# md_ver10_1.net
KiCad netlist of a schematic drawn in EAGLE
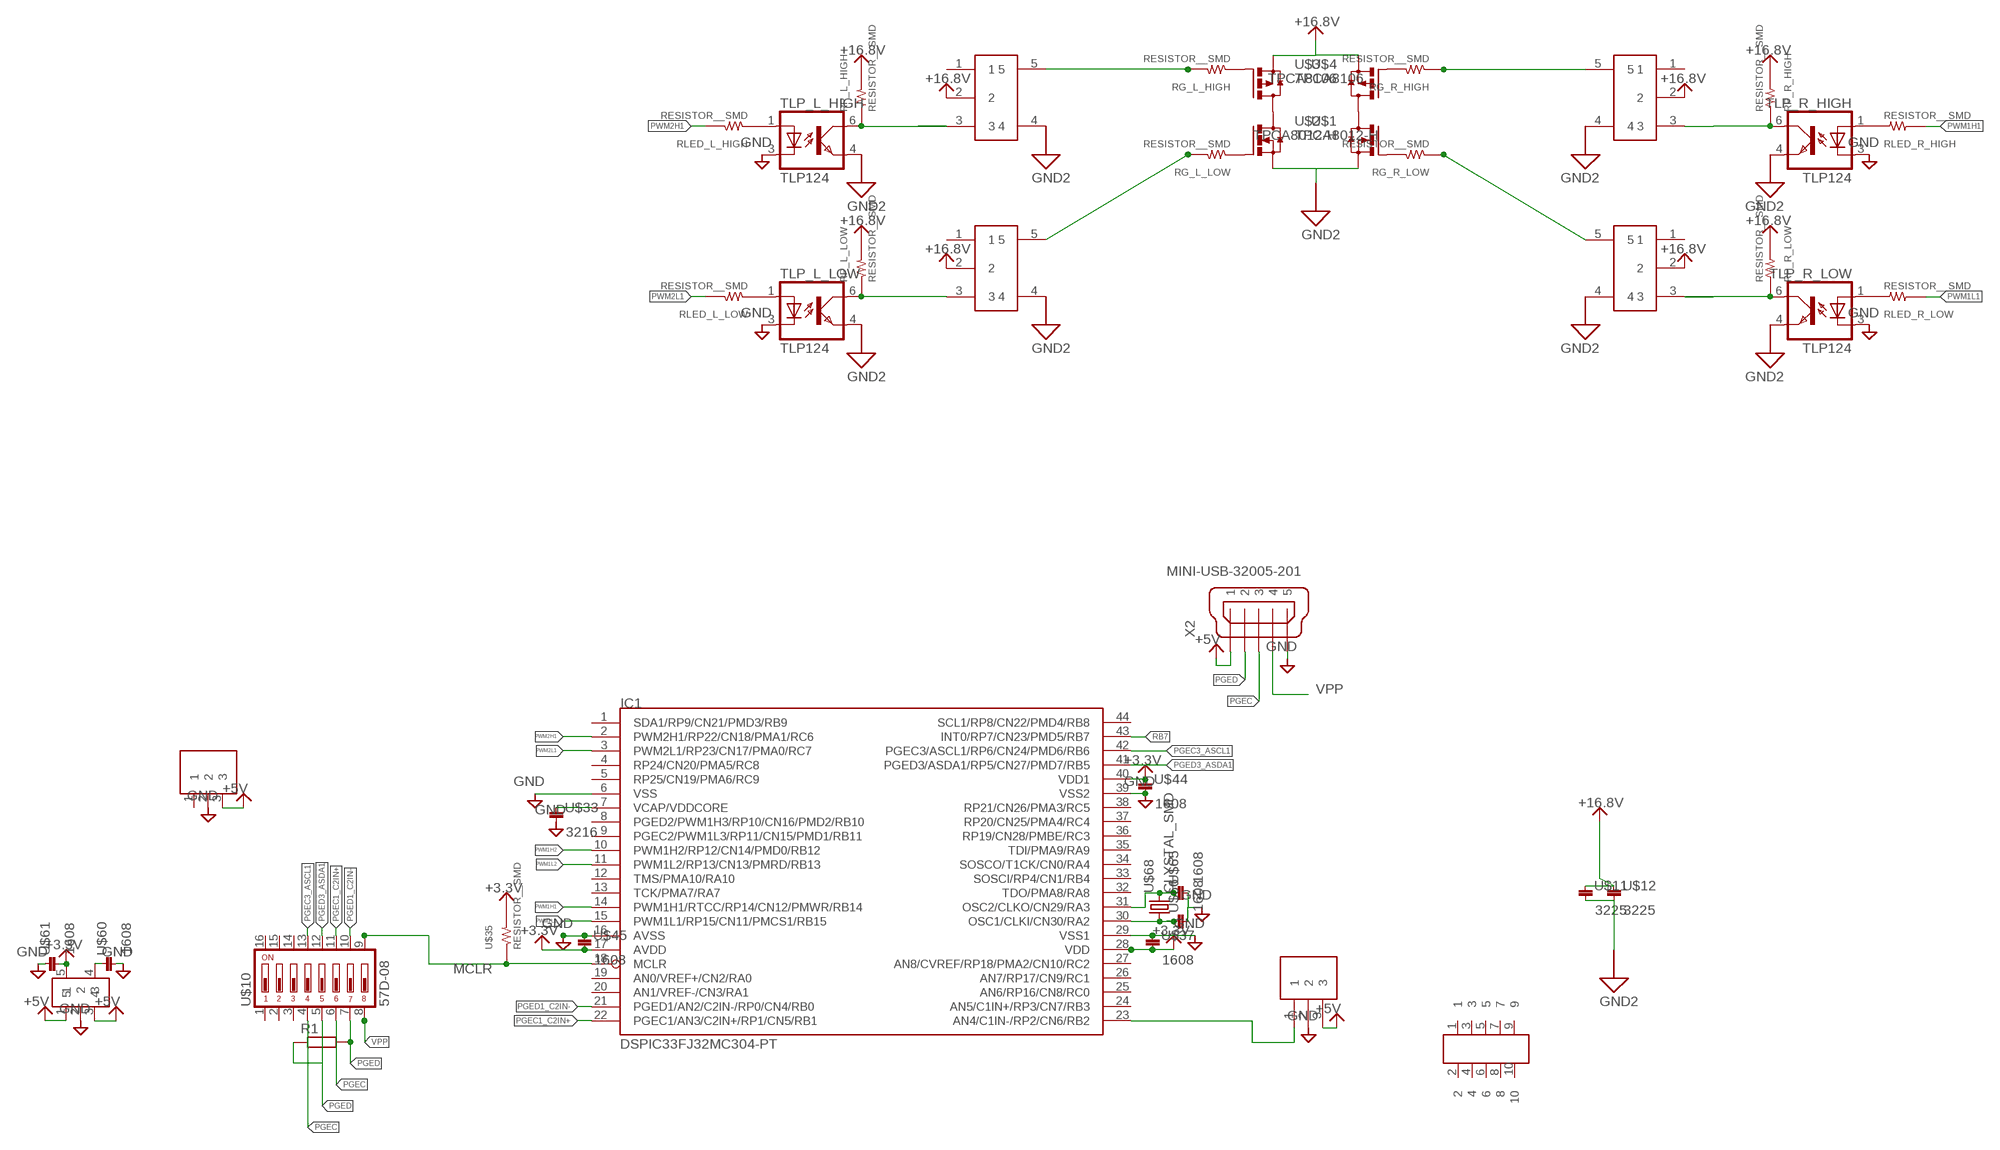
[diagram p0: schematic, sheet 1]

(export (version "E")
  (design (tool "Eeschema 10.0.6"))
  (components
    (comp (ref "IC1")
      (value "DSPIC33FJ32MC304-PT")
      (footprint "eagle-import:TQFP44")
      (libsource (lib "eagle-import") (part "DSPIC33FJ32MC304-PT"))
    )
    (comp (ref "IC_L_HIGH")
      (value "MCP1415")
      (footprint "eagle-import:SOT23-5L")
      (libsource (lib "eagle-import") (part "MCP1415"))
    )
    (comp (ref "IC_L_LOW")
      (value "MCP1415")
      (footprint "eagle-import:SOT23-5L")
      (libsource (lib "eagle-import") (part "MCP1415"))
    )
    (comp (ref "IC_R_HIGH")
      (value "MCP1415")
      (footprint "eagle-import:SOT23-5L")
      (libsource (lib "eagle-import") (part "MCP1415"))
    )
    (comp (ref "IC_R_LOW")
      (value "MCP1415")
      (footprint "eagle-import:SOT23-5L")
      (libsource (lib "eagle-import") (part "MCP1415"))
    )
    (comp (ref "R1")
      (value "R-EU_R3216")
      (footprint "eagle-import:R3216")
      (libsource (lib "eagle-import") (part "R-EU_R3216"))
    )
    (comp (ref "RG_L_HIGH")
      (value "RESISTOR__SMD")
      (footprint "eagle-import:1608")
      (libsource (lib "eagle-import") (part "RESISTOR__SMD"))
    )
    (comp (ref "RG_L_LOW")
      (value "RESISTOR__SMD")
      (footprint "eagle-import:1608")
      (libsource (lib "eagle-import") (part "RESISTOR__SMD"))
    )
    (comp (ref "RG_R_HIGH")
      (value "RESISTOR__SMD")
      (footprint "eagle-import:1608")
      (libsource (lib "eagle-import") (part "RESISTOR__SMD"))
    )
    (comp (ref "RG_R_LOW")
      (value "RESISTOR__SMD")
      (footprint "eagle-import:1608")
      (libsource (lib "eagle-import") (part "RESISTOR__SMD"))
    )
    (comp (ref "RLED_L_HIGH")
      (value "RESISTOR__SMD")
      (footprint "eagle-import:1608")
      (libsource (lib "eagle-import") (part "RESISTOR__SMD"))
    )
    (comp (ref "RLED_L_LOW")
      (value "RESISTOR__SMD")
      (footprint "eagle-import:1608")
      (libsource (lib "eagle-import") (part "RESISTOR__SMD"))
    )
    (comp (ref "RLED_R_HIGH")
      (value "RESISTOR__SMD")
      (footprint "eagle-import:1608")
      (libsource (lib "eagle-import") (part "RESISTOR__SMD"))
    )
    (comp (ref "RLED_R_LOW")
      (value "RESISTOR__SMD")
      (footprint "eagle-import:1608")
      (libsource (lib "eagle-import") (part "RESISTOR__SMD"))
    )
    (comp (ref "RP_L_HIGH")
      (value "RESISTOR__SMD")
      (footprint "eagle-import:1608")
      (libsource (lib "eagle-import") (part "RESISTOR__SMD"))
    )
    (comp (ref "RP_L_LOW")
      (value "RESISTOR__SMD")
      (footprint "eagle-import:1608")
      (libsource (lib "eagle-import") (part "RESISTOR__SMD"))
    )
    (comp (ref "RP_R_HIGH")
      (value "RESISTOR__SMD")
      (footprint "eagle-import:1608")
      (libsource (lib "eagle-import") (part "RESISTOR__SMD"))
    )
    (comp (ref "RP_R_LOW")
      (value "RESISTOR__SMD")
      (footprint "eagle-import:1608")
      (libsource (lib "eagle-import") (part "RESISTOR__SMD"))
    )
    (comp (ref "TLP_L_HIGH")
      (value "TLP124")
      (footprint "eagle-import:11−4C1")
      (libsource (lib "eagle-import") (part "TLP124"))
    )
    (comp (ref "TLP_L_LOW")
      (value "TLP124")
      (footprint "eagle-import:11−4C1")
      (libsource (lib "eagle-import") (part "TLP124"))
    )
    (comp (ref "TLP_R_HIGH")
      (value "TLP124")
      (footprint "eagle-import:11−4C1")
      (libsource (lib "eagle-import") (part "TLP124"))
    )
    (comp (ref "TLP_R_LOW")
      (value "TLP124")
      (footprint "eagle-import:11−4C1")
      (libsource (lib "eagle-import") (part "TLP124"))
    )
    (comp (ref "U$1")
      (value "TPCA8012-H")
      (footprint "eagle-import:2-5Q1A")
      (libsource (lib "eagle-import") (part "TPCA8012-H"))
    )
    (comp (ref "U$2")
      (value "TPCA8012-H")
      (footprint "eagle-import:2-5Q1A")
      (libsource (lib "eagle-import") (part "TPCA8012-H"))
    )
    (comp (ref "U$3")
      (value "TPCA8106")
      (footprint "eagle-import:2-5Q1A")
      (libsource (lib "eagle-import") (part "TPCA8106"))
    )
    (comp (ref "U$4")
      (value "TPCA8106")
      (footprint "eagle-import:2-5Q1A")
      (libsource (lib "eagle-import") (part "TPCA8106"))
    )
    (comp (ref "U$7")
      (value "ＰＬ－ＩＲＭ")
      (footprint "eagle-import:ＰＬ－ＩＲＭ")
      (libsource (lib "eagle-import") (part "ＰＬ－ＩＲＭ"))
    )
    (comp (ref "U$8")
      (value "Ｒ－７８Ｅ５．０")
      (footprint "eagle-import:Ｒ－７８Ｅ５．０")
      (libsource (lib "eagle-import") (part "Ｒ－７８Ｅ５．０"))
    )
    (comp (ref "U$9")
      (value "TAR5SB")
      (footprint "eagle-import:SSOP5-P-0.95")
      (libsource (lib "eagle-import") (part "TAR5SB"))
    )
    (comp (ref "U$10")
      (value "57D-08")
      (footprint "eagle-import:57D")
      (libsource (lib "eagle-import") (part "57D-08"))
    )
    (comp (ref "U$11")
      (value "3225")
      (footprint "eagle-import:3225")
      (libsource (lib "eagle-import") (part "3225"))
    )
    (comp (ref "U$12")
      (value "3225")
      (footprint "eagle-import:3225")
      (libsource (lib "eagle-import") (part "3225"))
    )
    (comp (ref "U$15")
      (value "PIN_HEADER_52")
      (footprint "eagle-import:PIN_HEADER_5_2")
      (libsource (lib "eagle-import") (part "PIN_HEADER_52"))
    )
    (comp (ref "U$33")
      (value "3216")
      (footprint "eagle-import:3216")
      (libsource (lib "eagle-import") (part "3216"))
    )
    (comp (ref "U$35")
      (value "RESISTOR__SMD")
      (footprint "eagle-import:1608")
      (libsource (lib "eagle-import") (part "RESISTOR__SMD"))
    )
    (comp (ref "U$37")
      (value "1608")
      (footprint "eagle-import:1608")
      (libsource (lib "eagle-import") (part "1608"))
    )
    (comp (ref "U$44")
      (value "1608")
      (footprint "eagle-import:1608")
      (libsource (lib "eagle-import") (part "1608"))
    )
    (comp (ref "U$45")
      (value "1608")
      (footprint "eagle-import:1608")
      (libsource (lib "eagle-import") (part "1608"))
    )
    (comp (ref "U$60")
      (value "1608")
      (footprint "eagle-import:1608")
      (libsource (lib "eagle-import") (part "1608"))
    )
    (comp (ref "U$61")
      (value "1608")
      (footprint "eagle-import:1608")
      (libsource (lib "eagle-import") (part "1608"))
    )
    (comp (ref "U$65")
      (value "1608")
      (footprint "eagle-import:1608")
      (libsource (lib "eagle-import") (part "1608"))
    )
    (comp (ref "U$66")
      (value "1608")
      (footprint "eagle-import:1608")
      (libsource (lib "eagle-import") (part "1608"))
    )
    (comp (ref "U$68")
      (value "CLYSTAL_SMD")
      (footprint "eagle-import:CRYSTAL_SMD")
      (libsource (lib "eagle-import") (part "CLYSTAL_SMD"))
    )
    (comp (ref "X2")
      (value "MINI-USB-32005-201")
      (footprint "eagle-import:32005-201")
      (libsource (lib "eagle-import") (part "MINI-USB-32005-201"))
    )
  )
  (nets
    (net (code "1") (name "+3.3V") (class "Default")
      (node (ref "IC1") (pin "17") (pinfunction "AVDD_17") (pintype "power_in"))
      (node (ref "IC1") (pin "28") (pinfunction "VDD_28") (pintype "power_in"))
      (node (ref "IC1") (pin "40") (pinfunction "VDD1_40") (pintype "power_in"))
      (node (ref "U$35") (pin "2") (pinfunction "P$2_2") (pintype "passive"))
      (node (ref "U$37") (pin "P$2") (pinfunction "2_P$2") (pintype "passive"))
      (node (ref "U$44") (pin "P$1") (pinfunction "1_P$1") (pintype "passive"))
      (node (ref "U$45") (pin "P$2") (pinfunction "2_P$2") (pintype "passive"))
      (node (ref "U$61") (pin "P$2") (pinfunction "2_P$2") (pintype "passive"))
      (node (ref "U$9") (pin "5") (pinfunction "5_5") (pintype "bidirectional"))
    )
    (net (code "2") (name "+5V") (class "Default")
      (node (ref "U$7") (pin "3") (pinfunction "3_3") (pintype "bidirectional"))
      (node (ref "U$8") (pin "3") (pinfunction "3_3") (pintype "bidirectional"))
      (node (ref "U$9") (pin "1") (pinfunction "1_1") (pintype "bidirectional"))
      (node (ref "U$9") (pin "3") (pinfunction "3_3") (pintype "bidirectional"))
      (node (ref "X2") (pin "1") (pinfunction "1_1") (pintype "passive"))
    )
    (net (code "3") (name "+16.8V") (class "Default")
      (node (ref "IC_L_HIGH") (pin "2") (pinfunction "2_2") (pintype "bidirectional"))
      (node (ref "IC_L_LOW") (pin "2") (pinfunction "2_2") (pintype "bidirectional"))
      (node (ref "IC_R_HIGH") (pin "2") (pinfunction "2_2") (pintype "bidirectional"))
      (node (ref "IC_R_LOW") (pin "2") (pinfunction "2_2") (pintype "bidirectional"))
      (node (ref "RP_L_HIGH") (pin "2") (pinfunction "P$2_2") (pintype "passive"))
      (node (ref "RP_L_LOW") (pin "2") (pinfunction "P$2_2") (pintype "passive"))
      (node (ref "RP_R_HIGH") (pin "2") (pinfunction "P$2_2") (pintype "passive"))
      (node (ref "RP_R_LOW") (pin "2") (pinfunction "P$2_2") (pintype "passive"))
      (node (ref "U$11") (pin "P$1") (pinfunction "1_P$1") (pintype "passive"))
      (node (ref "U$12") (pin "P$1") (pinfunction "1_P$1") (pintype "passive"))
      (node (ref "U$3") (pin "1") (pinfunction "S_1") (pintype "passive"))
      (node (ref "U$3") (pin "2") (pinfunction "S_2") (pintype "passive"))
      (node (ref "U$3") (pin "3") (pinfunction "S_3") (pintype "passive"))
      (node (ref "U$4") (pin "1") (pinfunction "S_1") (pintype "passive"))
      (node (ref "U$4") (pin "2") (pinfunction "S_2") (pintype "passive"))
      (node (ref "U$4") (pin "3") (pinfunction "S_3") (pintype "passive"))
    )
    (net (code "4") (name "/MCLR") (class "Default")
      (node (ref "IC1") (pin "18") (pinfunction "MCLR_18") (pintype "input"))
      (node (ref "U$10") (pin "9") (pinfunction "9_9") (pintype "passive"))
      (node (ref "U$35") (pin "1") (pinfunction "P$1_1") (pintype "passive"))
    )
    (net (code "5") (name "GND") (class "Default")
      (node (ref "IC1") (pin "16") (pinfunction "AVSS_16") (pintype "power_in"))
      (node (ref "IC1") (pin "29") (pinfunction "VSS1_29") (pintype "power_in"))
      (node (ref "IC1") (pin "39") (pinfunction "VSS2_39") (pintype "power_in"))
      (node (ref "IC1") (pin "6") (pinfunction "VSS_6") (pintype "power_in"))
      (node (ref "TLP_L_HIGH") (pin "3") (pinfunction "C_3") (pintype "passive"))
      (node (ref "TLP_L_LOW") (pin "3") (pinfunction "C_3") (pintype "passive"))
      (node (ref "TLP_R_HIGH") (pin "3") (pinfunction "C_3") (pintype "passive"))
      (node (ref "TLP_R_LOW") (pin "3") (pinfunction "C_3") (pintype "passive"))
      (node (ref "U$33") (pin "P$2") (pinfunction "2_P$2") (pintype "passive"))
      (node (ref "U$37") (pin "P$1") (pinfunction "1_P$1") (pintype "passive"))
      (node (ref "U$44") (pin "P$2") (pinfunction "2_P$2") (pintype "passive"))
      (node (ref "U$45") (pin "P$1") (pinfunction "1_P$1") (pintype "passive"))
      (node (ref "U$60") (pin "P$2") (pinfunction "2_P$2") (pintype "passive"))
      (node (ref "U$61") (pin "P$1") (pinfunction "1_P$1") (pintype "passive"))
      (node (ref "U$65") (pin "P$2") (pinfunction "2_P$2") (pintype "passive"))
      (node (ref "U$66") (pin "P$2") (pinfunction "2_P$2") (pintype "passive"))
      (node (ref "U$7") (pin "2") (pinfunction "2_2") (pintype "bidirectional"))
      (node (ref "U$8") (pin "2") (pinfunction "2_2") (pintype "bidirectional"))
      (node (ref "U$9") (pin "2") (pinfunction "2_2") (pintype "bidirectional"))
      (node (ref "X2") (pin "5") (pinfunction "5_5") (pintype "passive"))
    )
    (net (code "6") (name "GND2") (class "Default")
      (node (ref "IC_L_HIGH") (pin "4") (pinfunction "4_4") (pintype "bidirectional"))
      (node (ref "IC_L_LOW") (pin "4") (pinfunction "4_4") (pintype "bidirectional"))
      (node (ref "IC_R_HIGH") (pin "4") (pinfunction "4_4") (pintype "bidirectional"))
      (node (ref "IC_R_LOW") (pin "4") (pinfunction "4_4") (pintype "bidirectional"))
      (node (ref "TLP_L_HIGH") (pin "4") (pinfunction "EMIT_4") (pintype "passive"))
      (node (ref "TLP_L_LOW") (pin "4") (pinfunction "EMIT_4") (pintype "passive"))
      (node (ref "TLP_R_HIGH") (pin "4") (pinfunction "EMIT_4") (pintype "passive"))
      (node (ref "TLP_R_LOW") (pin "4") (pinfunction "EMIT_4") (pintype "passive"))
      (node (ref "U$1") (pin "1") (pinfunction "S_1") (pintype "passive"))
      (node (ref "U$1") (pin "2") (pinfunction "S_2") (pintype "passive"))
      (node (ref "U$1") (pin "3") (pinfunction "S_3") (pintype "passive"))
      (node (ref "U$11") (pin "P$2") (pinfunction "2_P$2") (pintype "passive"))
      (node (ref "U$12") (pin "P$2") (pinfunction "2_P$2") (pintype "passive"))
      (node (ref "U$2") (pin "1") (pinfunction "S_1") (pintype "passive"))
      (node (ref "U$2") (pin "2") (pinfunction "S_2") (pintype "passive"))
      (node (ref "U$2") (pin "3") (pinfunction "S_3") (pintype "passive"))
    )
    (net (code "7") (name "Net-(IC1-AN4{slash}C1IN-{slash}RP2{slash}CN6{slash}RB2)") (class "Default")
      (node (ref "IC1") (pin "23") (pinfunction "AN4/C1IN-/RP2/CN6/RB2_23") (pintype "bidirectional"))
      (node (ref "U$7") (pin "1") (pinfunction "1_1") (pintype "bidirectional"))
    )
    (net (code "8") (name "Net-(IC1-OSC1{slash}CLKI{slash}CN30{slash}RA2)") (class "Default")
      (node (ref "IC1") (pin "30") (pinfunction "OSC1/CLKI/CN30/RA2_30") (pintype "bidirectional"))
      (node (ref "U$66") (pin "P$1") (pinfunction "1_P$1") (pintype "passive"))
      (node (ref "U$68") (pin "1") (pinfunction "1_1") (pintype "passive"))
    )
    (net (code "9") (name "Net-(IC1-OSC2{slash}CLKO{slash}CN29{slash}RA3)") (class "Default")
      (node (ref "IC1") (pin "31") (pinfunction "OSC2/CLKO/CN29/RA3_31") (pintype "bidirectional"))
      (node (ref "U$65") (pin "P$1") (pinfunction "1_P$1") (pintype "passive"))
      (node (ref "U$68") (pin "2") (pinfunction "2_2") (pintype "passive"))
    )
    (net (code "10") (name "Net-(IC1-VCAP{slash}VDDCORE)") (class "Default")
      (node (ref "IC1") (pin "7") (pinfunction "VCAP/VDDCORE_7") (pintype "power_in"))
      (node (ref "U$33") (pin "P$1") (pinfunction "1_P$1") (pintype "passive"))
    )
    (net (code "11") (name "Net-(RG_L_HIGH-P$1)") (class "Default")
      (node (ref "RG_L_HIGH") (pin "1") (pinfunction "P$1_1") (pintype "passive"))
      (node (ref "U$3") (pin "4") (pinfunction "G_4") (pintype "passive"))
    )
    (net (code "12") (name "Net-(RG_L_HIGH-P$2)") (class "Default")
      (node (ref "IC_L_HIGH") (pin "5") (pinfunction "5_5") (pintype "bidirectional"))
      (node (ref "RG_L_HIGH") (pin "2") (pinfunction "P$2_2") (pintype "passive"))
    )
    (net (code "13") (name "Net-(RG_L_LOW-P$1)") (class "Default")
      (node (ref "RG_L_LOW") (pin "1") (pinfunction "P$1_1") (pintype "passive"))
      (node (ref "U$2") (pin "4") (pinfunction "G_4") (pintype "passive"))
    )
    (net (code "14") (name "Net-(RG_L_LOW-P$2)") (class "Default")
      (node (ref "IC_L_LOW") (pin "5") (pinfunction "5_5") (pintype "bidirectional"))
      (node (ref "RG_L_LOW") (pin "2") (pinfunction "P$2_2") (pintype "passive"))
    )
    (net (code "15") (name "Net-(RG_R_HIGH-P$1)") (class "Default")
      (node (ref "IC_R_HIGH") (pin "5") (pinfunction "5_5") (pintype "bidirectional"))
      (node (ref "RG_R_HIGH") (pin "1") (pinfunction "P$1_1") (pintype "passive"))
    )
    (net (code "16") (name "Net-(RG_R_HIGH-P$2)") (class "Default")
      (node (ref "RG_R_HIGH") (pin "2") (pinfunction "P$2_2") (pintype "passive"))
      (node (ref "U$4") (pin "4") (pinfunction "G_4") (pintype "passive"))
    )
    (net (code "17") (name "Net-(RG_R_LOW-P$1)") (class "Default")
      (node (ref "IC_R_LOW") (pin "5") (pinfunction "5_5") (pintype "bidirectional"))
      (node (ref "RG_R_LOW") (pin "1") (pinfunction "P$1_1") (pintype "passive"))
    )
    (net (code "18") (name "Net-(RG_R_LOW-P$2)") (class "Default")
      (node (ref "RG_R_LOW") (pin "2") (pinfunction "P$2_2") (pintype "passive"))
      (node (ref "U$1") (pin "4") (pinfunction "G_4") (pintype "passive"))
    )
    (net (code "19") (name "Net-(RLED_L_HIGH-P$1)") (class "Default")
      (node (ref "RLED_L_HIGH") (pin "1") (pinfunction "P$1_1") (pintype "passive"))
      (node (ref "TLP_L_HIGH") (pin "1") (pinfunction "A_1") (pintype "passive"))
    )
    (net (code "20") (name "Net-(RLED_L_LOW-P$1)") (class "Default")
      (node (ref "RLED_L_LOW") (pin "1") (pinfunction "P$1_1") (pintype "passive"))
      (node (ref "TLP_L_LOW") (pin "1") (pinfunction "A_1") (pintype "passive"))
    )
    (net (code "21") (name "Net-(RLED_R_HIGH-P$1)") (class "Default")
      (node (ref "RLED_R_HIGH") (pin "1") (pinfunction "P$1_1") (pintype "passive"))
      (node (ref "TLP_R_HIGH") (pin "1") (pinfunction "A_1") (pintype "passive"))
    )
    (net (code "22") (name "Net-(RLED_R_LOW-P$1)") (class "Default")
      (node (ref "RLED_R_LOW") (pin "1") (pinfunction "P$1_1") (pintype "passive"))
      (node (ref "TLP_R_LOW") (pin "1") (pinfunction "A_1") (pintype "passive"))
    )
    (net (code "23") (name "Net-(RP_L_HIGH-P$1)") (class "Default")
      (node (ref "IC_L_HIGH") (pin "3") (pinfunction "3_3") (pintype "bidirectional"))
      (node (ref "RP_L_HIGH") (pin "1") (pinfunction "P$1_1") (pintype "passive"))
      (node (ref "TLP_L_HIGH") (pin "6") (pinfunction "COL_6") (pintype "passive"))
    )
    (net (code "24") (name "Net-(RP_L_LOW-P$1)") (class "Default")
      (node (ref "IC_L_LOW") (pin "3") (pinfunction "3_3") (pintype "bidirectional"))
      (node (ref "RP_L_LOW") (pin "1") (pinfunction "P$1_1") (pintype "passive"))
      (node (ref "TLP_L_LOW") (pin "6") (pinfunction "COL_6") (pintype "passive"))
    )
    (net (code "25") (name "Net-(RP_R_HIGH-P$1)") (class "Default")
      (node (ref "IC_R_HIGH") (pin "3") (pinfunction "3_3") (pintype "bidirectional"))
      (node (ref "RP_R_HIGH") (pin "1") (pinfunction "P$1_1") (pintype "passive"))
      (node (ref "TLP_R_HIGH") (pin "6") (pinfunction "COL_6") (pintype "passive"))
    )
    (net (code "26") (name "Net-(RP_R_LOW-P$1)") (class "Default")
      (node (ref "IC_R_LOW") (pin "3") (pinfunction "3_3") (pintype "bidirectional"))
      (node (ref "RP_R_LOW") (pin "1") (pinfunction "P$1_1") (pintype "passive"))
      (node (ref "TLP_R_LOW") (pin "6") (pinfunction "COL_6") (pintype "passive"))
    )
    (net (code "27") (name "Net-(U$1-D-Pad5)") (class "Default")
      (node (ref "U$1") (pin "5") (pinfunction "D_5") (pintype "passive"))
      (node (ref "U$1") (pin "6") (pinfunction "D_6") (pintype "passive"))
      (node (ref "U$1") (pin "7") (pinfunction "D_7") (pintype "passive"))
      (node (ref "U$1") (pin "8") (pinfunction "D_8") (pintype "passive"))
      (node (ref "U$4") (pin "5") (pinfunction "D_5") (pintype "passive"))
      (node (ref "U$4") (pin "6") (pinfunction "D_6") (pintype "passive"))
      (node (ref "U$4") (pin "7") (pinfunction "D_7") (pintype "passive"))
      (node (ref "U$4") (pin "8") (pinfunction "D_8") (pintype "passive"))
    )
    (net (code "28") (name "Net-(U$2-D-Pad5)") (class "Default")
      (node (ref "U$2") (pin "5") (pinfunction "D_5") (pintype "passive"))
      (node (ref "U$2") (pin "6") (pinfunction "D_6") (pintype "passive"))
      (node (ref "U$2") (pin "7") (pinfunction "D_7") (pintype "passive"))
      (node (ref "U$2") (pin "8") (pinfunction "D_8") (pintype "passive"))
      (node (ref "U$3") (pin "5") (pinfunction "D_5") (pintype "passive"))
      (node (ref "U$3") (pin "6") (pinfunction "D_6") (pintype "passive"))
      (node (ref "U$3") (pin "7") (pinfunction "D_7") (pintype "passive"))
      (node (ref "U$3") (pin "8") (pinfunction "D_8") (pintype "passive"))
    )
    (net (code "29") (name "Net-(U$60-1)") (class "Default")
      (node (ref "U$60") (pin "P$1") (pinfunction "1_P$1") (pintype "passive"))
      (node (ref "U$9") (pin "4") (pinfunction "4_4") (pintype "bidirectional"))
    )
    (net (code "30") (name "PGEC") (class "Default")
      (node (ref "U$10") (pin "4") (pinfunction "4_4") (pintype "passive"))
      (node (ref "U$10") (pin "6") (pinfunction "6_6") (pintype "passive"))
      (node (ref "X2") (pin "3") (pinfunction "3_3") (pintype "passive"))
    )
    (net (code "31") (name "PGEC1_C2IN+") (class "Default")
      (node (ref "IC1") (pin "22") (pinfunction "PGEC1/AN3/C2IN+/RP1/CN5/RB1_22") (pintype "bidirectional"))
      (node (ref "U$10") (pin "11") (pinfunction "11_11") (pintype "passive"))
    )
    (net (code "32") (name "PGEC3_ASCL1") (class "Default")
      (node (ref "IC1") (pin "42") (pinfunction "PGEC3/ASCL1/RP6/CN24/PMD6/RB6_42") (pintype "bidirectional"))
      (node (ref "U$10") (pin "13") (pinfunction "13_13") (pintype "passive"))
    )
    (net (code "33") (name "PGED") (class "Default")
      (node (ref "R1") (pin "1") (pinfunction "1_1") (pintype "passive"))
      (node (ref "R1") (pin "2") (pinfunction "2_2") (pintype "passive"))
      (node (ref "U$10") (pin "5") (pinfunction "5_5") (pintype "passive"))
      (node (ref "U$10") (pin "7") (pinfunction "7_7") (pintype "passive"))
      (node (ref "X2") (pin "2") (pinfunction "2_2") (pintype "passive"))
    )
    (net (code "34") (name "PGED1_C2IN-") (class "Default")
      (node (ref "IC1") (pin "21") (pinfunction "PGED1/AN2/C2IN-/RP0/CN4/RB0_21") (pintype "bidirectional"))
      (node (ref "U$10") (pin "10") (pinfunction "10_10") (pintype "passive"))
    )
    (net (code "35") (name "PGED3_ASDA1") (class "Default")
      (node (ref "IC1") (pin "41") (pinfunction "PGED3/ASDA1/RP5/CN27/PMD7/RB5_41") (pintype "bidirectional"))
      (node (ref "U$10") (pin "12") (pinfunction "12_12") (pintype "passive"))
    )
    (net (code "36") (name "PWM1H1") (class "Default")
      (node (ref "IC1") (pin "14") (pinfunction "PWM1H1/RTCC/RP14/CN12/PMWR/RB14_14") (pintype "bidirectional"))
      (node (ref "RLED_R_HIGH") (pin "2") (pinfunction "P$2_2") (pintype "passive"))
    )
    (net (code "37") (name "PWM1H2") (class "Default")
      (node (ref "IC1") (pin "10") (pinfunction "PWM1H2/RP12/CN14/PMD0/RB12_10") (pintype "bidirectional"))
    )
    (net (code "38") (name "PWM1L1") (class "Default")
      (node (ref "IC1") (pin "15") (pinfunction "PWM1L1/RP15/CN11/PMCS1/RB15_15") (pintype "bidirectional"))
      (node (ref "RLED_R_LOW") (pin "2") (pinfunction "P$2_2") (pintype "passive"))
    )
    (net (code "39") (name "PWM1L2") (class "Default")
      (node (ref "IC1") (pin "11") (pinfunction "PWM1L2/RP13/CN13/PMRD/RB13_11") (pintype "bidirectional"))
    )
    (net (code "40") (name "PWM2H1") (class "Default")
      (node (ref "IC1") (pin "2") (pinfunction "PWM2H1/RP22/CN18/PMA1/RC6_2") (pintype "bidirectional"))
      (node (ref "RLED_L_HIGH") (pin "2") (pinfunction "P$2_2") (pintype "passive"))
    )
    (net (code "41") (name "PWM2L1") (class "Default")
      (node (ref "IC1") (pin "3") (pinfunction "PWM2L1/RP23/CN17/PMA0/RC7_3") (pintype "bidirectional"))
      (node (ref "RLED_L_LOW") (pin "2") (pinfunction "P$2_2") (pintype "passive"))
    )
    (net (code "42") (name "RB7") (class "Default")
      (node (ref "IC1") (pin "43") (pinfunction "INT0/RP7/CN23/PMD5/RB7_43") (pintype "bidirectional"))
    )
    (net (code "43") (name "VPP") (class "Default")
      (node (ref "U$10") (pin "8") (pinfunction "8_8") (pintype "passive"))
      (node (ref "X2") (pin "4") (pinfunction "4_4") (pintype "passive"))
    )
    (net (code "44") (name "unconnected-(IC1-AN0{slash}VREF+{slash}CN2{slash}RA0-Pad19)") (class "Default")
      (node (ref "IC1") (pin "19") (pinfunction "AN0/VREF+/CN2/RA0_19") (pintype "bidirectional"))
    )
    (net (code "45") (name "unconnected-(IC1-AN1{slash}VREF-{slash}CN3{slash}RA1-Pad20)") (class "Default")
      (node (ref "IC1") (pin "20") (pinfunction "AN1/VREF-/CN3/RA1_20") (pintype "bidirectional"))
    )
    (net (code "46") (name "unconnected-(IC1-AN5{slash}C1IN+{slash}RP3{slash}CN7{slash}RB3-Pad24)") (class "Default")
      (node (ref "IC1") (pin "24") (pinfunction "AN5/C1IN+/RP3/CN7/RB3_24") (pintype "bidirectional"))
    )
    (net (code "47") (name "unconnected-(IC1-AN6{slash}RP16{slash}CN8{slash}RC0-Pad25)") (class "Default")
      (node (ref "IC1") (pin "25") (pinfunction "AN6/RP16/CN8/RC0_25") (pintype "bidirectional"))
    )
    (net (code "48") (name "unconnected-(IC1-AN7{slash}RP17{slash}CN9{slash}RC1-Pad26)") (class "Default")
      (node (ref "IC1") (pin "26") (pinfunction "AN7/RP17/CN9/RC1_26") (pintype "bidirectional"))
    )
    (net (code "49") (name "unconnected-(IC1-AN8{slash}CVREF{slash}RP18{slash}PMA2{slash}CN10{slash}RC2-Pad27)") (class "Default")
      (node (ref "IC1") (pin "27") (pinfunction "AN8/CVREF/RP18/PMA2/CN10/RC2_27") (pintype "bidirectional"))
    )
    (net (code "50") (name "unconnected-(IC1-PGEC2{slash}PWM1L3{slash}RP11{slash}CN15{slash}PMD1{slash}RB11-Pad9)") (class "Default")
      (node (ref "IC1") (pin "9") (pinfunction "PGEC2/PWM1L3/RP11/CN15/PMD1/RB11_9") (pintype "bidirectional"))
    )
    (net (code "51") (name "unconnected-(IC1-PGED2{slash}PWM1H3{slash}RP10{slash}CN16{slash}PMD2{slash}RB10-Pad8)") (class "Default")
      (node (ref "IC1") (pin "8") (pinfunction "PGED2/PWM1H3/RP10/CN16/PMD2/RB10_8") (pintype "bidirectional"))
    )
    (net (code "52") (name "unconnected-(IC1-RP19{slash}CN28{slash}PMBE{slash}RC3-Pad36)") (class "Default")
      (node (ref "IC1") (pin "36") (pinfunction "RP19/CN28/PMBE/RC3_36") (pintype "bidirectional"))
    )
    (net (code "53") (name "unconnected-(IC1-RP20{slash}CN25{slash}PMA4{slash}RC4-Pad37)") (class "Default")
      (node (ref "IC1") (pin "37") (pinfunction "RP20/CN25/PMA4/RC4_37") (pintype "bidirectional"))
    )
    (net (code "54") (name "unconnected-(IC1-RP21{slash}CN26{slash}PMA3{slash}RC5-Pad38)") (class "Default")
      (node (ref "IC1") (pin "38") (pinfunction "RP21/CN26/PMA3/RC5_38") (pintype "bidirectional"))
    )
    (net (code "55") (name "unconnected-(IC1-RP24{slash}CN20{slash}PMA5{slash}RC8-Pad4)") (class "Default")
      (node (ref "IC1") (pin "4") (pinfunction "RP24/CN20/PMA5/RC8_4") (pintype "bidirectional"))
    )
    (net (code "56") (name "unconnected-(IC1-RP25{slash}CN19{slash}PMA6{slash}RC9-Pad5)") (class "Default")
      (node (ref "IC1") (pin "5") (pinfunction "RP25/CN19/PMA6/RC9_5") (pintype "bidirectional"))
    )
    (net (code "57") (name "unconnected-(IC1-SCL1{slash}RP8{slash}CN22{slash}PMD4{slash}RB8-Pad44)") (class "Default")
      (node (ref "IC1") (pin "44") (pinfunction "SCL1/RP8/CN22/PMD4/RB8_44") (pintype "bidirectional"))
    )
    (net (code "58") (name "unconnected-(IC1-SDA1{slash}RP9{slash}CN21{slash}PMD3{slash}RB9-Pad1)") (class "Default")
      (node (ref "IC1") (pin "1") (pinfunction "SDA1/RP9/CN21/PMD3/RB9_1") (pintype "bidirectional"))
    )
    (net (code "59") (name "unconnected-(IC1-SOSCI{slash}RP4{slash}CN1{slash}RB4-Pad33)") (class "Default")
      (node (ref "IC1") (pin "33") (pinfunction "SOSCI/RP4/CN1/RB4_33") (pintype "bidirectional"))
    )
    (net (code "60") (name "unconnected-(IC1-SOSCO{slash}T1CK{slash}CN0{slash}RA4-Pad34)") (class "Default")
      (node (ref "IC1") (pin "34") (pinfunction "SOSCO/T1CK/CN0/RA4_34") (pintype "bidirectional"))
    )
    (net (code "61") (name "unconnected-(IC1-TCK{slash}PMA7{slash}RA7-Pad13)") (class "Default")
      (node (ref "IC1") (pin "13") (pinfunction "TCK/PMA7/RA7_13") (pintype "bidirectional"))
    )
    (net (code "62") (name "unconnected-(IC1-TDI{slash}PMA9{slash}RA9-Pad35)") (class "Default")
      (node (ref "IC1") (pin "35") (pinfunction "TDI/PMA9/RA9_35") (pintype "bidirectional"))
    )
    (net (code "63") (name "unconnected-(IC1-TDO{slash}PMA8{slash}RA8-Pad32)") (class "Default")
      (node (ref "IC1") (pin "32") (pinfunction "TDO/PMA8/RA8_32") (pintype "bidirectional"))
    )
    (net (code "64") (name "unconnected-(IC1-TMS{slash}PMA10{slash}RA10-Pad12)") (class "Default")
      (node (ref "IC1") (pin "12") (pinfunction "TMS/PMA10/RA10_12") (pintype "bidirectional"))
    )
    (net (code "65") (name "unconnected-(IC_L_HIGH-Pad1)") (class "Default")
      (node (ref "IC_L_HIGH") (pin "1") (pinfunction "1_1") (pintype "bidirectional"))
    )
    (net (code "66") (name "unconnected-(IC_L_LOW-Pad1)") (class "Default")
      (node (ref "IC_L_LOW") (pin "1") (pinfunction "1_1") (pintype "bidirectional"))
    )
    (net (code "67") (name "unconnected-(IC_R_HIGH-Pad1)") (class "Default")
      (node (ref "IC_R_HIGH") (pin "1") (pinfunction "1_1") (pintype "bidirectional"))
    )
    (net (code "68") (name "unconnected-(IC_R_LOW-Pad1)") (class "Default")
      (node (ref "IC_R_LOW") (pin "1") (pinfunction "1_1") (pintype "bidirectional"))
    )
    (net (code "69") (name "unconnected-(U$8-Pad1)") (class "Default")
      (node (ref "U$8") (pin "1") (pinfunction "1_1") (pintype "bidirectional"))
    )
    (net (code "70") (name "unconnected-(U$10-Pad1)") (class "Default")
      (node (ref "U$10") (pin "1") (pinfunction "1_1") (pintype "passive"))
    )
    (net (code "71") (name "unconnected-(U$10-Pad2)") (class "Default")
      (node (ref "U$10") (pin "2") (pinfunction "2_2") (pintype "passive"))
    )
    (net (code "72") (name "unconnected-(U$10-Pad3)") (class "Default")
      (node (ref "U$10") (pin "3") (pinfunction "3_3") (pintype "passive"))
    )
    (net (code "73") (name "unconnected-(U$10-Pad14)") (class "Default")
      (node (ref "U$10") (pin "14") (pinfunction "14_14") (pintype "passive"))
    )
    (net (code "74") (name "unconnected-(U$10-Pad15)") (class "Default")
      (node (ref "U$10") (pin "15") (pinfunction "15_15") (pintype "passive"))
    )
    (net (code "75") (name "unconnected-(U$10-Pad16)") (class "Default")
      (node (ref "U$10") (pin "16") (pinfunction "16_16") (pintype "passive"))
    )
    (net (code "76") (name "unconnected-(U$15-Pad1)") (class "Default")
      (node (ref "U$15") (pin "1") (pinfunction "1_1") (pintype "bidirectional"))
    )
    (net (code "77") (name "unconnected-(U$15-Pad2)") (class "Default")
      (node (ref "U$15") (pin "2") (pinfunction "2_2") (pintype "bidirectional"))
    )
    (net (code "78") (name "unconnected-(U$15-Pad3)") (class "Default")
      (node (ref "U$15") (pin "3") (pinfunction "3_3") (pintype "bidirectional"))
    )
    (net (code "79") (name "unconnected-(U$15-Pad4)") (class "Default")
      (node (ref "U$15") (pin "4") (pinfunction "4_4") (pintype "bidirectional"))
    )
    (net (code "80") (name "unconnected-(U$15-Pad5)") (class "Default")
      (node (ref "U$15") (pin "5") (pinfunction "5_5") (pintype "bidirectional"))
    )
    (net (code "81") (name "unconnected-(U$15-Pad6)") (class "Default")
      (node (ref "U$15") (pin "6") (pinfunction "6_6") (pintype "bidirectional"))
    )
    (net (code "82") (name "unconnected-(U$15-Pad7)") (class "Default")
      (node (ref "U$15") (pin "7") (pinfunction "7_7") (pintype "bidirectional"))
    )
    (net (code "83") (name "unconnected-(U$15-Pad8)") (class "Default")
      (node (ref "U$15") (pin "8") (pinfunction "8_8") (pintype "bidirectional"))
    )
    (net (code "84") (name "unconnected-(U$15-Pad9)") (class "Default")
      (node (ref "U$15") (pin "9") (pinfunction "9_9") (pintype "bidirectional"))
    )
    (net (code "85") (name "unconnected-(U$15-Pad10)") (class "Default")
      (node (ref "U$15") (pin "10") (pinfunction "10_10") (pintype "bidirectional"))
    )
  )
)
